# CAN_BUS.net
KiCad netlist of a schematic drawn in Altium Designer
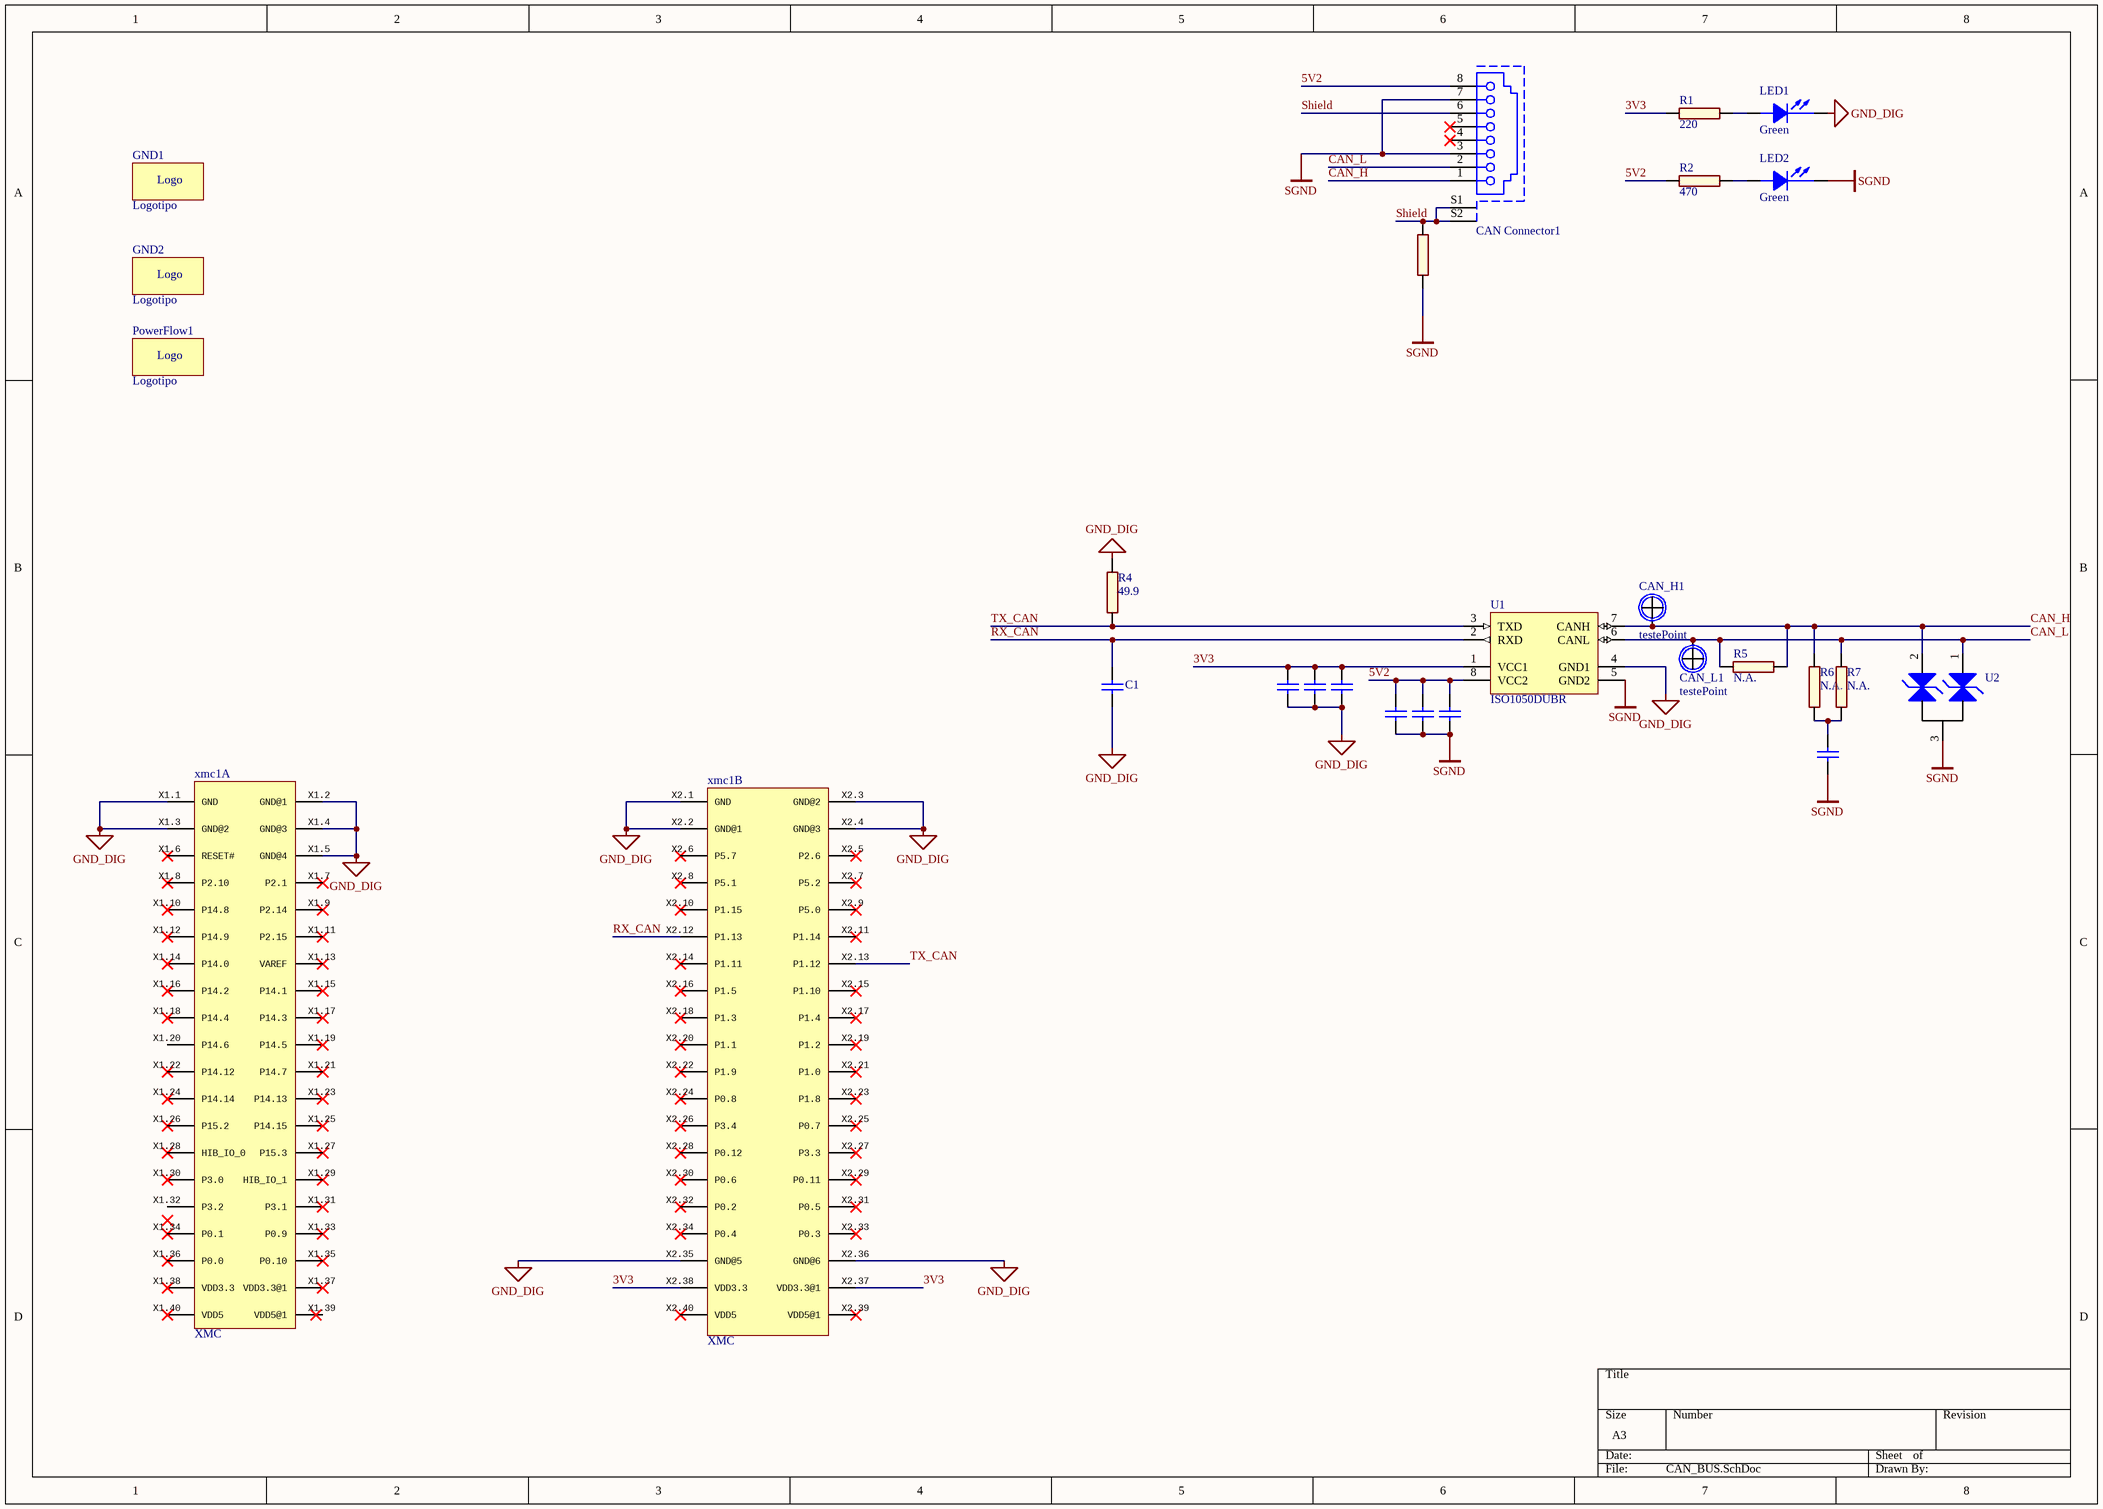
[diagram p0: CAN_BUS.SchDoc]

(export (version "E")
  (design (tool "Eeschema 10.0.6"))
  (components
    (comp (ref "C1")
      (value "Capacitor")
      (footprint "CAPC_0805")
      (fields (field (name "LCSC PART #") "C1794"))
      (libsource (lib "myLibraryAltium") (part "Capacitor"))
    )
    (comp (ref "C2")
      (value "Capacitor")
      (footprint "CAPC_0805")
      (fields (field (name "LCSC PART #") "C28323"))
      (libsource (lib "myLibraryAltium") (part "Capacitor"))
    )
    (comp (ref "C3")
      (value "Capacitor")
      (footprint "CAPC_0805")
      (fields (field (name "LCSC PART #") "C49678"))
      (libsource (lib "myLibraryAltium") (part "Capacitor"))
    )
    (comp (ref "C4")
      (value "Capacitor")
      (footprint "CAPC_0805")
      (fields (field (name "LCSC PART #") "C1710"))
      (libsource (lib "myLibraryAltium") (part "Capacitor"))
    )
    (comp (ref "C5")
      (value "Capacitor")
      (footprint "CAPC_0805")
      (fields (field (name "LCSC PART #") "C28323"))
      (libsource (lib "myLibraryAltium") (part "Capacitor"))
    )
    (comp (ref "C6")
      (value "Capacitor")
      (footprint "CAPC_0805")
      (fields (field (name "LCSC PART #") "C49678"))
      (libsource (lib "myLibraryAltium") (part "Capacitor"))
    )
    (comp (ref "C7")
      (value "Capacitor")
      (footprint "CAPC_0805")
      (fields (field (name "LCSC PART #") "C1710"))
      (libsource (lib "myLibraryAltium") (part "Capacitor"))
    )
    (comp (ref "C8")
      (value "Capacitor")
      (footprint "CAPC_0805")
      (libsource (lib "myLibraryAltium") (part "Capacitor"))
    )
    (comp (ref "CAN Connector1")
      (value "61500814221")
      (footprint "61500814221")
      (description "Modular Jack Horizontal Shielded 8P8C Tab Down WR-MJ")
      (fields (field (name "PUBLISHER") "Wurth Elektronik"))
      (libsource (lib "Modular Jack Connector_WR-MJ") (part "61500814221"))
    )
    (comp (ref "CAN_H1")
      (value "testePoint")
      (footprint "PAD 2.5MM - FURO 1.25MM")
      (libsource (lib "myLibraryAltium") (part "testePoint"))
    )
    (comp (ref "CAN_L1")
      (value "testePoint")
      (footprint "PAD 2.5MM - FURO 1.25MM")
      (libsource (lib "myLibraryAltium") (part "testePoint"))
    )
    (comp (ref "GND1")
      (value "Logotipo")
      (footprint "Dangerous_Logo")
      (libsource (lib "myLibraryAltium") (part "Logotipo"))
    )
    (comp (ref "GND2")
      (value "Logotipo")
      (footprint "Dangerous_Logo")
      (libsource (lib "myLibraryAltium") (part "Logotipo"))
    )
    (comp (ref "LED1")
      (value "Green")
      (footprint "CD2012-0805")
      (description "LED 2X1.2MM 570NM GN WTR CLR SMD")
      (fields (field (name "MANUFACTURER") "Kingbright") (field (name "MPN") "APT2012CGCK"))
      (libsource (lib "myLibraryAltium") (part "LED_GREEN"))
    )
    (comp (ref "LED2")
      (value "Green")
      (footprint "CD2012-0805")
      (description "LED 2X1.2MM 570NM GN WTR CLR SMD")
      (fields (field (name "MANUFACTURER") "Kingbright") (field (name "MPN") "APT2012CGCK"))
      (libsource (lib "myLibraryAltium") (part "LED_GREEN"))
    )
    (comp (ref "PowerFlow1")
      (value "Logotipo")
      (footprint "PowerFlow_LOGO")
      (libsource (lib "myLibraryAltium") (part "Logotipo"))
    )
    (comp (ref "R1")
      (value "220")
      (footprint "RESC_0805")
      (description "Thick film resistor, SMD 0402, 1/16W, 1%")
      (fields (field (name "MANUFACTURER") "Generic") (field (name "LCSC PART #") "C17557"))
      (libsource (lib "") (part "R2_1"))
    )
    (comp (ref "R2")
      (value "470")
      (footprint "RESC_0805")
      (description "Thick film resistor, SMD 0402, 1/16W, 1%")
      (fields (field (name "MANUFACTURER") "Generic"))
      (libsource (lib "") (part "R2_1"))
    )
    (comp (ref "R3")
      (value "N.A.")
      (footprint "RESC_0805")
      (description "Thick film resistor, SMD 0402, 1/16W, 1%")
      (fields (field (name "MANUFACTURER") "Generic"))
      (libsource (lib "myLibraryAltium") (part "R2"))
    )
    (comp (ref "R4")
      (value "49.9")
      (footprint "RESC_0805")
      (description "Thick film resistor, SMD 0402, 1/16W, 1%")
      (fields (field (name "MANUFACTURER") "Generic") (field (name "LCSC PART #") "C17720"))
      (libsource (lib "myLibraryAltium") (part "R2"))
    )
    (comp (ref "R5")
      (value "N.A.")
      (footprint "RESC_0805")
      (description "Thick film resistor, SMD 0402, 1/16W, 1%")
      (fields (field (name "MANUFACTURER") "Generic"))
      (libsource (lib "") (part "R2_2"))
    )
    (comp (ref "R6")
      (value "N.A.")
      (footprint "RESC_0805")
      (description "Thick film resistor, SMD 0402, 1/16W, 1%")
      (fields (field (name "MANUFACTURER") "Generic") (field (name "LCSC PART #") "C17802"))
      (libsource (lib "myLibraryAltium") (part "R2"))
    )
    (comp (ref "R7")
      (value "N.A.")
      (footprint "RESC_0805")
      (description "Thick film resistor, SMD 0402, 1/16W, 1%")
      (fields (field (name "MANUFACTURER") "Generic") (field (name "LCSC PART #") "C17802"))
      (libsource (lib "myLibraryAltium") (part "R2"))
    )
    (comp (ref "U1")
      (value "ISO1050DUBR")
      (footprint "DUB8_M")
      (description "Isolated CAN Transceiver, -55 to 105 degC, 8-pin SOP (DUB), Green (RoHS & no Sb/Br)")
      (fields (field (name "LCSC PART #") "C16428"))
      (libsource (lib "myLibraryAltium") (part "ISO1050DUBR"))
    )
    (comp (ref "U2")
      (value "Diode_TVS_Array")
      (footprint "SOT23-3")
      (fields (field (name "LCSC PART #") "C151237"))
      (libsource (lib "myLibraryAltium") (part "Diode_TVS_Array"))
    )
    (comp (ref "xmc1")
      (value "XMC")
      (footprint "XMC4500_Relax_Lite")
      (libsource (lib "myLibraryAltium") (part "XMC"))
    )
  )
  (nets
    (net (code "1") (name "/3V3") (class "Default")
      (node (ref "C2") (pin "2") (pinfunction "2_2") (pintype "passive"))
      (node (ref "C3") (pin "2") (pinfunction "2_2") (pintype "passive"))
      (node (ref "C4") (pin "2") (pinfunction "2_2") (pintype "passive"))
      (node (ref "R1") (pin "1") (pinfunction "1_1") (pintype "passive"))
      (node (ref "U1") (pin "1") (pinfunction "VCC1_1") (pintype "power_in"))
      (node (ref "xmc1") (pin "X2.37") (pinfunction "VDD3.3@1_X2.37") (pintype "passive"))
      (node (ref "xmc1") (pin "X2.38") (pinfunction "VDD3.3_X2.38") (pintype "passive"))
    )
    (net (code "2") (name "/5V2") (class "Default")
      (node (ref "C5") (pin "2") (pinfunction "2_2") (pintype "passive"))
      (node (ref "C6") (pin "2") (pinfunction "2_2") (pintype "passive"))
      (node (ref "C7") (pin "2") (pinfunction "2_2") (pintype "passive"))
      (node (ref "CAN Connector1") (pin "8") (pinfunction "8_8") (pintype "passive"))
      (node (ref "R2") (pin "1") (pinfunction "1_1") (pintype "passive"))
      (node (ref "U1") (pin "8") (pinfunction "VCC2_8") (pintype "power_in"))
    )
    (net (code "3") (name "/CAN_H") (class "Default")
      (node (ref "CAN Connector1") (pin "1") (pinfunction "1_1") (pintype "passive"))
      (node (ref "CAN_H1") (pin "1") (pinfunction "1_1") (pintype "passive"))
      (node (ref "R5") (pin "1") (pinfunction "1_1") (pintype "passive"))
      (node (ref "R6") (pin "2") (pinfunction "2_2") (pintype "passive"))
      (node (ref "U1") (pin "7") (pinfunction "CANH_7") (pintype "bidirectional"))
      (node (ref "U2") (pin "2") (pinfunction "2_2") (pintype "passive"))
    )
    (net (code "4") (name "/CAN_L") (class "Default")
      (node (ref "CAN Connector1") (pin "2") (pinfunction "2_2") (pintype "passive"))
      (node (ref "CAN_L1") (pin "1") (pinfunction "1_1") (pintype "passive"))
      (node (ref "R5") (pin "2") (pinfunction "2_2") (pintype "passive"))
      (node (ref "R7") (pin "2") (pinfunction "2_2") (pintype "passive"))
      (node (ref "U1") (pin "6") (pinfunction "CANL_6") (pintype "bidirectional"))
      (node (ref "U2") (pin "1") (pinfunction "1_1") (pintype "passive"))
    )
    (net (code "5") (name "/RX_CAN") (class "Default")
      (node (ref "C1") (pin "2") (pinfunction "2_2") (pintype "passive"))
      (node (ref "U1") (pin "2") (pinfunction "RXD_2") (pintype "output"))
      (node (ref "xmc1") (pin "X2.12") (pinfunction "P1.13_X2.12") (pintype "passive"))
    )
    (net (code "6") (name "/Shield") (class "Default")
      (node (ref "CAN Connector1") (pin "6") (pinfunction "6_6") (pintype "passive"))
      (node (ref "CAN Connector1") (pin "S1") (pinfunction "Shield_S1") (pintype "passive"))
      (node (ref "CAN Connector1") (pin "S2") (pinfunction "Shield_S2") (pintype "passive"))
      (node (ref "R3") (pin "2") (pinfunction "2_2") (pintype "passive"))
    )
    (net (code "7") (name "/TX_CAN") (class "Default")
      (node (ref "R4") (pin "1") (pinfunction "1_1") (pintype "passive"))
      (node (ref "U1") (pin "3") (pinfunction "TXD_3") (pintype "input"))
      (node (ref "xmc1") (pin "X2.13") (pinfunction "P1.12_X2.13") (pintype "passive"))
    )
    (net (code "8") (name "GND_DIG") (class "Default")
      (node (ref "C1") (pin "1") (pinfunction "1_1") (pintype "passive"))
      (node (ref "C2") (pin "1") (pinfunction "1_1") (pintype "passive"))
      (node (ref "C3") (pin "1") (pinfunction "1_1") (pintype "passive"))
      (node (ref "C4") (pin "1") (pinfunction "1_1") (pintype "passive"))
      (node (ref "LED1") (pin "C") (pinfunction "CATHODE_C") (pintype "passive"))
      (node (ref "R4") (pin "2") (pinfunction "2_2") (pintype "passive"))
      (node (ref "U1") (pin "4") (pinfunction "GND1_4") (pintype "power_in"))
      (node (ref "xmc1") (pin "X1.1") (pinfunction "GND_X1.1") (pintype "passive"))
      (node (ref "xmc1") (pin "X1.2") (pinfunction "GND@1_X1.2") (pintype "passive"))
      (node (ref "xmc1") (pin "X1.3") (pinfunction "GND@2_X1.3") (pintype "passive"))
      (node (ref "xmc1") (pin "X1.4") (pinfunction "GND@3_X1.4") (pintype "passive"))
      (node (ref "xmc1") (pin "X1.5") (pinfunction "GND@4_X1.5") (pintype "passive"))
      (node (ref "xmc1") (pin "X2.1") (pinfunction "GND_X2.1") (pintype "passive"))
      (node (ref "xmc1") (pin "X2.2") (pinfunction "GND@1_X2.2") (pintype "passive"))
      (node (ref "xmc1") (pin "X2.3") (pinfunction "GND@2_X2.3") (pintype "passive"))
      (node (ref "xmc1") (pin "X2.35") (pinfunction "GND@5_X2.35") (pintype "passive"))
      (node (ref "xmc1") (pin "X2.36") (pinfunction "GND@6_X2.36") (pintype "passive"))
      (node (ref "xmc1") (pin "X2.4") (pinfunction "GND@3_X2.4") (pintype "passive"))
    )
    (net (code "9") (name "Net-(C8-Pad1)") (class "Default")
      (node (ref "C8") (pin "1") (pinfunction "1_1") (pintype "passive"))
      (node (ref "R6") (pin "1") (pinfunction "1_1") (pintype "passive"))
      (node (ref "R7") (pin "1") (pinfunction "1_1") (pintype "passive"))
    )
    (net (code "10") (name "Net-(LED1-ANODE)") (class "Default")
      (node (ref "LED1") (pin "A") (pinfunction "ANODE_A") (pintype "passive"))
      (node (ref "R1") (pin "2") (pinfunction "2_2") (pintype "passive"))
    )
    (net (code "11") (name "Net-(LED2-ANODE)") (class "Default")
      (node (ref "LED2") (pin "A") (pinfunction "ANODE_A") (pintype "passive"))
      (node (ref "R2") (pin "2") (pinfunction "2_2") (pintype "passive"))
    )
    (net (code "12") (name "SGND") (class "Default")
      (node (ref "C5") (pin "1") (pinfunction "1_1") (pintype "passive"))
      (node (ref "C6") (pin "1") (pinfunction "1_1") (pintype "passive"))
      (node (ref "C7") (pin "1") (pinfunction "1_1") (pintype "passive"))
      (node (ref "C8") (pin "2") (pinfunction "2_2") (pintype "passive"))
      (node (ref "CAN Connector1") (pin "3") (pinfunction "3_3") (pintype "passive"))
      (node (ref "CAN Connector1") (pin "7") (pinfunction "7_7") (pintype "passive"))
      (node (ref "LED2") (pin "C") (pinfunction "CATHODE_C") (pintype "passive"))
      (node (ref "R3") (pin "1") (pinfunction "1_1") (pintype "passive"))
      (node (ref "U1") (pin "5") (pinfunction "GND2_5") (pintype "power_in"))
      (node (ref "U2") (pin "3") (pinfunction "3_3") (pintype "passive"))
    )
    (net (code "13") (name "unconnected-(CAN Connector1-Pad4)") (class "Default")
      (node (ref "CAN Connector1") (pin "4") (pinfunction "4_4") (pintype "passive+no_connect"))
    )
    (net (code "14") (name "unconnected-(CAN Connector1-Pad5)") (class "Default")
      (node (ref "CAN Connector1") (pin "5") (pinfunction "5_5") (pintype "passive+no_connect"))
    )
    (net (code "15") (name "unconnected-(xmc1A-HIB_IO_0-PadX1.28)") (class "Default")
      (node (ref "xmc1") (pin "X1.28") (pinfunction "HIB_IO_0_X1.28") (pintype "passive+no_connect"))
    )
    (net (code "16") (name "unconnected-(xmc1A-HIB_IO_1-PadX1.29)") (class "Default")
      (node (ref "xmc1") (pin "X1.29") (pinfunction "HIB_IO_1_X1.29") (pintype "passive+no_connect"))
    )
    (net (code "17") (name "unconnected-(xmc1A-P0.0-PadX1.36)") (class "Default")
      (node (ref "xmc1") (pin "X1.36") (pinfunction "P0.0_X1.36") (pintype "passive+no_connect"))
    )
    (net (code "18") (name "unconnected-(xmc1A-P0.1-PadX1.34)") (class "Default")
      (node (ref "xmc1") (pin "X1.34") (pinfunction "P0.1_X1.34") (pintype "passive+no_connect"))
    )
    (net (code "19") (name "unconnected-(xmc1A-P0.9-PadX1.33)") (class "Default")
      (node (ref "xmc1") (pin "X1.33") (pinfunction "P0.9_X1.33") (pintype "passive+no_connect"))
    )
    (net (code "20") (name "unconnected-(xmc1A-P0.10-PadX1.35)") (class "Default")
      (node (ref "xmc1") (pin "X1.35") (pinfunction "P0.10_X1.35") (pintype "passive+no_connect"))
    )
    (net (code "21") (name "unconnected-(xmc1A-P2.1-PadX1.7)") (class "Default")
      (node (ref "xmc1") (pin "X1.7") (pinfunction "P2.1_X1.7") (pintype "passive+no_connect"))
    )
    (net (code "22") (name "unconnected-(xmc1A-P2.10-PadX1.8)") (class "Default")
      (node (ref "xmc1") (pin "X1.8") (pinfunction "P2.10_X1.8") (pintype "passive+no_connect"))
    )
    (net (code "23") (name "unconnected-(xmc1A-P2.14-PadX1.9)") (class "Default")
      (node (ref "xmc1") (pin "X1.9") (pinfunction "P2.14_X1.9") (pintype "passive+no_connect"))
    )
    (net (code "24") (name "unconnected-(xmc1A-P2.15-PadX1.11)") (class "Default")
      (node (ref "xmc1") (pin "X1.11") (pinfunction "P2.15_X1.11") (pintype "passive+no_connect"))
    )
    (net (code "25") (name "unconnected-(xmc1A-P3.0-PadX1.30)") (class "Default")
      (node (ref "xmc1") (pin "X1.30") (pinfunction "P3.0_X1.30") (pintype "passive+no_connect"))
    )
    (net (code "26") (name "unconnected-(xmc1A-P3.1-PadX1.31)") (class "Default")
      (node (ref "xmc1") (pin "X1.31") (pinfunction "P3.1_X1.31") (pintype "passive+no_connect"))
    )
    (net (code "27") (name "unconnected-(xmc1A-P3.2-PadX1.32)") (class "Default")
      (node (ref "xmc1") (pin "X1.32") (pinfunction "P3.2_X1.32") (pintype "passive"))
    )
    (net (code "28") (name "unconnected-(xmc1A-P14.0-PadX1.14)") (class "Default")
      (node (ref "xmc1") (pin "X1.14") (pinfunction "P14.0_X1.14") (pintype "passive+no_connect"))
    )
    (net (code "29") (name "unconnected-(xmc1A-P14.1-PadX1.15)") (class "Default")
      (node (ref "xmc1") (pin "X1.15") (pinfunction "P14.1_X1.15") (pintype "passive+no_connect"))
    )
    (net (code "30") (name "unconnected-(xmc1A-P14.2-PadX1.16)") (class "Default")
      (node (ref "xmc1") (pin "X1.16") (pinfunction "P14.2_X1.16") (pintype "passive+no_connect"))
    )
    (net (code "31") (name "unconnected-(xmc1A-P14.3-PadX1.17)") (class "Default")
      (node (ref "xmc1") (pin "X1.17") (pinfunction "P14.3_X1.17") (pintype "passive+no_connect"))
    )
    (net (code "32") (name "unconnected-(xmc1A-P14.4-PadX1.18)") (class "Default")
      (node (ref "xmc1") (pin "X1.18") (pinfunction "P14.4_X1.18") (pintype "passive+no_connect"))
    )
    (net (code "33") (name "unconnected-(xmc1A-P14.5-PadX1.19)") (class "Default")
      (node (ref "xmc1") (pin "X1.19") (pinfunction "P14.5_X1.19") (pintype "passive+no_connect"))
    )
    (net (code "34") (name "unconnected-(xmc1A-P14.6-PadX1.20)") (class "Default")
      (node (ref "xmc1") (pin "X1.20") (pinfunction "P14.6_X1.20") (pintype "passive"))
    )
    (net (code "35") (name "unconnected-(xmc1A-P14.7-PadX1.21)") (class "Default")
      (node (ref "xmc1") (pin "X1.21") (pinfunction "P14.7_X1.21") (pintype "passive+no_connect"))
    )
    (net (code "36") (name "unconnected-(xmc1A-P14.8-PadX1.10)") (class "Default")
      (node (ref "xmc1") (pin "X1.10") (pinfunction "P14.8_X1.10") (pintype "passive+no_connect"))
    )
    (net (code "37") (name "unconnected-(xmc1A-P14.9-PadX1.12)") (class "Default")
      (node (ref "xmc1") (pin "X1.12") (pinfunction "P14.9_X1.12") (pintype "passive+no_connect"))
    )
    (net (code "38") (name "unconnected-(xmc1A-P14.12-PadX1.22)") (class "Default")
      (node (ref "xmc1") (pin "X1.22") (pinfunction "P14.12_X1.22") (pintype "passive+no_connect"))
    )
    (net (code "39") (name "unconnected-(xmc1A-P14.13-PadX1.23)") (class "Default")
      (node (ref "xmc1") (pin "X1.23") (pinfunction "P14.13_X1.23") (pintype "passive+no_connect"))
    )
    (net (code "40") (name "unconnected-(xmc1A-P14.14-PadX1.24)") (class "Default")
      (node (ref "xmc1") (pin "X1.24") (pinfunction "P14.14_X1.24") (pintype "passive+no_connect"))
    )
    (net (code "41") (name "unconnected-(xmc1A-P14.15-PadX1.25)") (class "Default")
      (node (ref "xmc1") (pin "X1.25") (pinfunction "P14.15_X1.25") (pintype "passive+no_connect"))
    )
    (net (code "42") (name "unconnected-(xmc1A-P15.2-PadX1.26)") (class "Default")
      (node (ref "xmc1") (pin "X1.26") (pinfunction "P15.2_X1.26") (pintype "passive+no_connect"))
    )
    (net (code "43") (name "unconnected-(xmc1A-P15.3-PadX1.27)") (class "Default")
      (node (ref "xmc1") (pin "X1.27") (pinfunction "P15.3_X1.27") (pintype "passive+no_connect"))
    )
    (net (code "44") (name "unconnected-(xmc1A-RESET#-PadX1.6)") (class "Default")
      (node (ref "xmc1") (pin "X1.6") (pinfunction "RESET#_X1.6") (pintype "passive+no_connect"))
    )
    (net (code "45") (name "unconnected-(xmc1A-VAREF-PadX1.13)") (class "Default")
      (node (ref "xmc1") (pin "X1.13") (pinfunction "VAREF_X1.13") (pintype "passive+no_connect"))
    )
    (net (code "46") (name "unconnected-(xmc1A-VDD3.3-PadX1.38)") (class "Default")
      (node (ref "xmc1") (pin "X1.38") (pinfunction "VDD3.3_X1.38") (pintype "passive+no_connect"))
    )
    (net (code "47") (name "unconnected-(xmc1A-VDD3.3@1-PadX1.37)") (class "Default")
      (node (ref "xmc1") (pin "X1.37") (pinfunction "VDD3.3@1_X1.37") (pintype "passive+no_connect"))
    )
    (net (code "48") (name "unconnected-(xmc1A-VDD5-PadX1.40)") (class "Default")
      (node (ref "xmc1") (pin "X1.40") (pinfunction "VDD5_X1.40") (pintype "passive+no_connect"))
    )
    (net (code "49") (name "unconnected-(xmc1A-VDD5@1-PadX1.39)") (class "Default")
      (node (ref "xmc1") (pin "X1.39") (pinfunction "VDD5@1_X1.39") (pintype "passive"))
    )
    (net (code "50") (name "unconnected-(xmc1B-P0.2-PadX2.32)") (class "Default")
      (node (ref "xmc1") (pin "X2.32") (pinfunction "P0.2_X2.32") (pintype "passive+no_connect"))
    )
    (net (code "51") (name "unconnected-(xmc1B-P0.3-PadX2.33)") (class "Default")
      (node (ref "xmc1") (pin "X2.33") (pinfunction "P0.3_X2.33") (pintype "passive+no_connect"))
    )
    (net (code "52") (name "unconnected-(xmc1B-P0.4-PadX2.34)") (class "Default")
      (node (ref "xmc1") (pin "X2.34") (pinfunction "P0.4_X2.34") (pintype "passive+no_connect"))
    )
    (net (code "53") (name "unconnected-(xmc1B-P0.5-PadX2.31)") (class "Default")
      (node (ref "xmc1") (pin "X2.31") (pinfunction "P0.5_X2.31") (pintype "passive+no_connect"))
    )
    (net (code "54") (name "unconnected-(xmc1B-P0.6-PadX2.30)") (class "Default")
      (node (ref "xmc1") (pin "X2.30") (pinfunction "P0.6_X2.30") (pintype "passive+no_connect"))
    )
    (net (code "55") (name "unconnected-(xmc1B-P0.7-PadX2.25)") (class "Default")
      (node (ref "xmc1") (pin "X2.25") (pinfunction "P0.7_X2.25") (pintype "passive+no_connect"))
    )
    (net (code "56") (name "unconnected-(xmc1B-P0.8-PadX2.24)") (class "Default")
      (node (ref "xmc1") (pin "X2.24") (pinfunction "P0.8_X2.24") (pintype "passive+no_connect"))
    )
    (net (code "57") (name "unconnected-(xmc1B-P0.11-PadX2.29)") (class "Default")
      (node (ref "xmc1") (pin "X2.29") (pinfunction "P0.11_X2.29") (pintype "passive+no_connect"))
    )
    (net (code "58") (name "unconnected-(xmc1B-P0.12-PadX2.28)") (class "Default")
      (node (ref "xmc1") (pin "X2.28") (pinfunction "P0.12_X2.28") (pintype "passive+no_connect"))
    )
    (net (code "59") (name "unconnected-(xmc1B-P1.0-PadX2.21)") (class "Default")
      (node (ref "xmc1") (pin "X2.21") (pinfunction "P1.0_X2.21") (pintype "passive+no_connect"))
    )
    (net (code "60") (name "unconnected-(xmc1B-P1.1-PadX2.20)") (class "Default")
      (node (ref "xmc1") (pin "X2.20") (pinfunction "P1.1_X2.20") (pintype "passive+no_connect"))
    )
    (net (code "61") (name "unconnected-(xmc1B-P1.2-PadX2.19)") (class "Default")
      (node (ref "xmc1") (pin "X2.19") (pinfunction "P1.2_X2.19") (pintype "passive+no_connect"))
    )
    (net (code "62") (name "unconnected-(xmc1B-P1.3-PadX2.18)") (class "Default")
      (node (ref "xmc1") (pin "X2.18") (pinfunction "P1.3_X2.18") (pintype "passive+no_connect"))
    )
    (net (code "63") (name "unconnected-(xmc1B-P1.4-PadX2.17)") (class "Default")
      (node (ref "xmc1") (pin "X2.17") (pinfunction "P1.4_X2.17") (pintype "passive+no_connect"))
    )
    (net (code "64") (name "unconnected-(xmc1B-P1.5-PadX2.16)") (class "Default")
      (node (ref "xmc1") (pin "X2.16") (pinfunction "P1.5_X2.16") (pintype "passive+no_connect"))
    )
    (net (code "65") (name "unconnected-(xmc1B-P1.8-PadX2.23)") (class "Default")
      (node (ref "xmc1") (pin "X2.23") (pinfunction "P1.8_X2.23") (pintype "passive+no_connect"))
    )
    (net (code "66") (name "unconnected-(xmc1B-P1.9-PadX2.22)") (class "Default")
      (node (ref "xmc1") (pin "X2.22") (pinfunction "P1.9_X2.22") (pintype "passive+no_connect"))
    )
    (net (code "67") (name "unconnected-(xmc1B-P1.10-PadX2.15)") (class "Default")
      (node (ref "xmc1") (pin "X2.15") (pinfunction "P1.10_X2.15") (pintype "passive+no_connect"))
    )
    (net (code "68") (name "unconnected-(xmc1B-P1.11-PadX2.14)") (class "Default")
      (node (ref "xmc1") (pin "X2.14") (pinfunction "P1.11_X2.14") (pintype "passive+no_connect"))
    )
    (net (code "69") (name "unconnected-(xmc1B-P1.14-PadX2.11)") (class "Default")
      (node (ref "xmc1") (pin "X2.11") (pinfunction "P1.14_X2.11") (pintype "passive+no_connect"))
    )
    (net (code "70") (name "unconnected-(xmc1B-P1.15-PadX2.10)") (class "Default")
      (node (ref "xmc1") (pin "X2.10") (pinfunction "P1.15_X2.10") (pintype "passive+no_connect"))
    )
    (net (code "71") (name "unconnected-(xmc1B-P2.6-PadX2.5)") (class "Default")
      (node (ref "xmc1") (pin "X2.5") (pinfunction "P2.6_X2.5") (pintype "passive+no_connect"))
    )
    (net (code "72") (name "unconnected-(xmc1B-P3.3-PadX2.27)") (class "Default")
      (node (ref "xmc1") (pin "X2.27") (pinfunction "P3.3_X2.27") (pintype "passive+no_connect"))
    )
    (net (code "73") (name "unconnected-(xmc1B-P3.4-PadX2.26)") (class "Default")
      (node (ref "xmc1") (pin "X2.26") (pinfunction "P3.4_X2.26") (pintype "passive+no_connect"))
    )
    (net (code "74") (name "unconnected-(xmc1B-P5.0-PadX2.9)") (class "Default")
      (node (ref "xmc1") (pin "X2.9") (pinfunction "P5.0_X2.9") (pintype "passive+no_connect"))
    )
    (net (code "75") (name "unconnected-(xmc1B-P5.1-PadX2.8)") (class "Default")
      (node (ref "xmc1") (pin "X2.8") (pinfunction "P5.1_X2.8") (pintype "passive+no_connect"))
    )
    (net (code "76") (name "unconnected-(xmc1B-P5.2-PadX2.7)") (class "Default")
      (node (ref "xmc1") (pin "X2.7") (pinfunction "P5.2_X2.7") (pintype "passive+no_connect"))
    )
    (net (code "77") (name "unconnected-(xmc1B-P5.7-PadX2.6)") (class "Default")
      (node (ref "xmc1") (pin "X2.6") (pinfunction "P5.7_X2.6") (pintype "passive+no_connect"))
    )
    (net (code "78") (name "unconnected-(xmc1B-VDD5-PadX2.40)") (class "Default")
      (node (ref "xmc1") (pin "X2.40") (pinfunction "VDD5_X2.40") (pintype "passive+no_connect"))
    )
    (net (code "79") (name "unconnected-(xmc1B-VDD5@1-PadX2.39)") (class "Default")
      (node (ref "xmc1") (pin "X2.39") (pinfunction "VDD5@1_X2.39") (pintype "passive+no_connect"))
    )
  )
)
